# Drive-motor_V1_0_2.net
KiCad netlist of a schematic drawn in Altium Designer
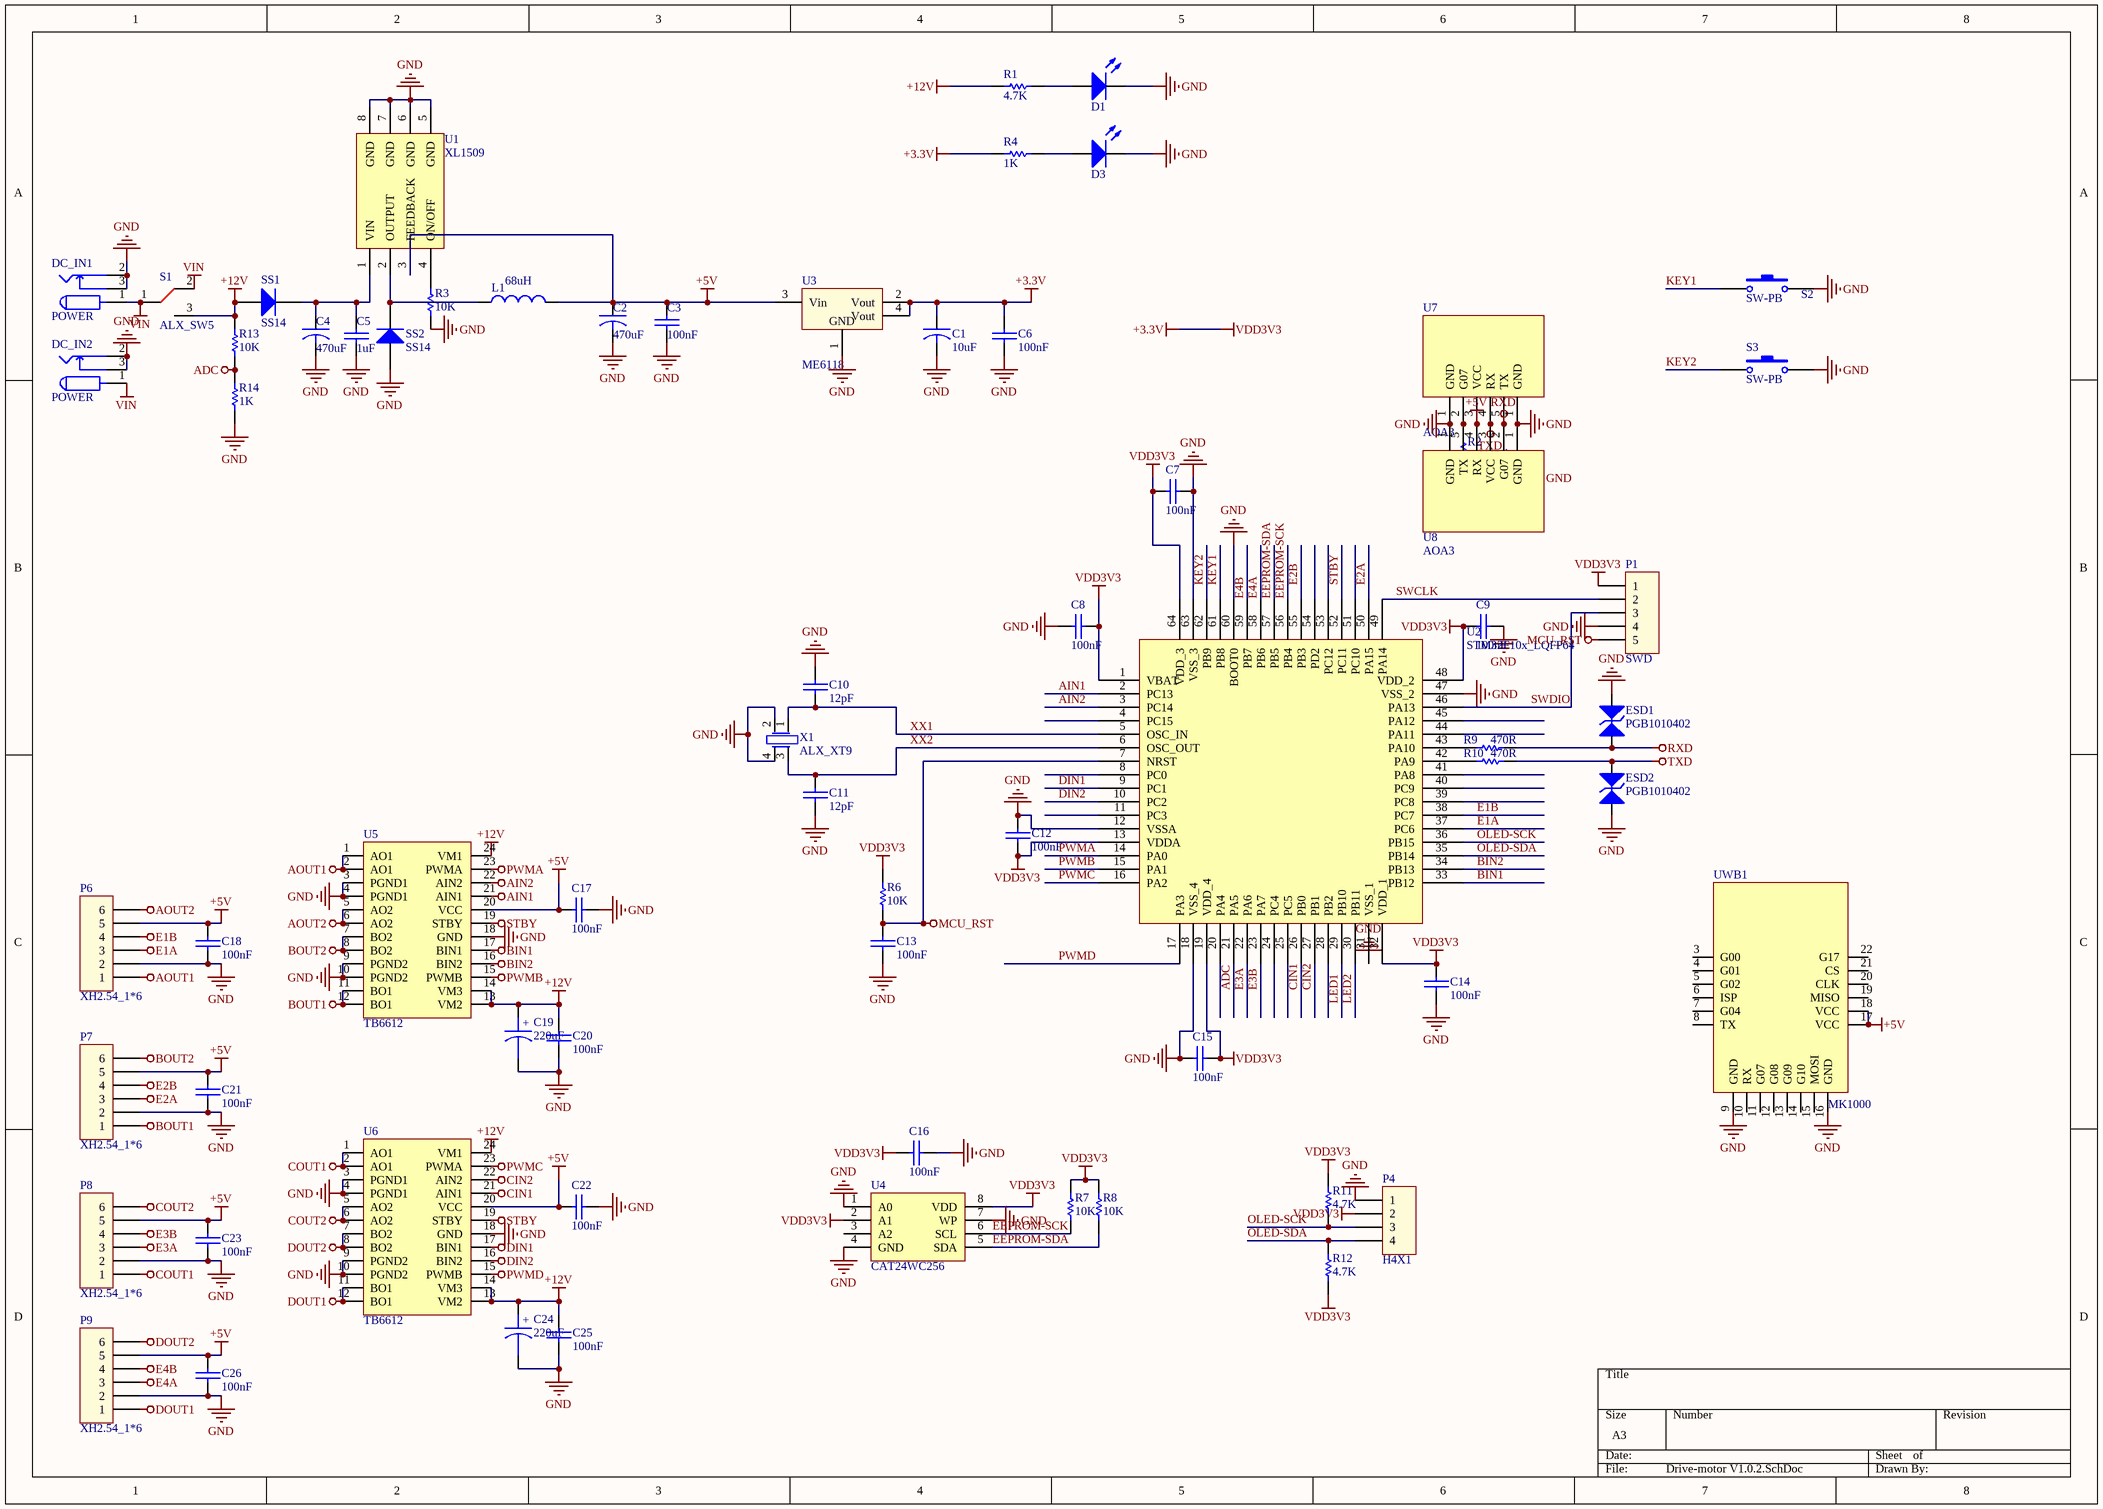
[diagram p0: Drive-motor V1.0.2.SchDoc]

(export (version "E")
  (design (tool "Eeschema 10.0.6"))
  (components
    (comp (ref "C1")
      (value "10uF")
      (footprint "ALX_E")
      (description "Capacitor")
      (libsource (lib "MIAO") (part "ALX_CAPACITOR"))
    )
    (comp (ref "C2")
      (value "470uF")
      (footprint "CAP POL [35V]")
      (description "Capacitor")
      (libsource (lib "MIAO") (part "ALX_CAPACITOR"))
    )
    (comp (ref "C3")
      (value "100nF")
      (footprint "ALX_0603C")
      (description "Capacitor")
      (libsource (lib "MIAO") (part "ALX_CAP"))
    )
    (comp (ref "C4")
      (value "470uF")
      (footprint "CAP POL [35V]")
      (description "Capacitor")
      (libsource (lib "MIAO") (part "ALX_CAPACITOR"))
    )
    (comp (ref "C5")
      (value "1uF")
      (footprint "ALX_0603C")
      (description "Capacitor")
      (libsource (lib "MIAO") (part "ALX_CAP"))
    )
    (comp (ref "C6")
      (value "100nF")
      (footprint "0603C")
      (description "Capacitor")
      (libsource (lib "MIAO") (part "ALX_CAP"))
    )
    (comp (ref "C7")
      (value "100nF")
      (footprint "0603C")
      (description "Capacitor")
      (libsource (lib "MIAO") (part "ALX_CAP"))
    )
    (comp (ref "C8")
      (value "100nF")
      (footprint "0603C")
      (description "Capacitor")
      (libsource (lib "MIAO") (part "ALX_CAP"))
    )
    (comp (ref "C9")
      (value "100nF")
      (footprint "0603C")
      (description "Capacitor")
      (libsource (lib "MIAO") (part "ALX_CAP"))
    )
    (comp (ref "C10")
      (value "12pF")
      (footprint "0603C")
      (description "Capacitor")
      (libsource (lib "MIAO") (part "ALX_CAP"))
    )
    (comp (ref "C11")
      (value "12pF")
      (footprint "0603C")
      (description "Capacitor")
      (libsource (lib "MIAO") (part "ALX_CAP"))
    )
    (comp (ref "C12")
      (value "100nF")
      (footprint "0603C")
      (description "Capacitor")
      (libsource (lib "MIAO") (part "ALX_CAP"))
    )
    (comp (ref "C13")
      (value "100nF")
      (footprint "0603C")
      (description "Capacitor")
      (libsource (lib "MIAO") (part "ALX_CAP"))
    )
    (comp (ref "C14")
      (value "100nF")
      (footprint "0603C")
      (description "Capacitor")
      (libsource (lib "MIAO") (part "ALX_CAP"))
    )
    (comp (ref "C15")
      (value "100nF")
      (footprint "0603C")
      (description "Capacitor")
      (libsource (lib "MIAO") (part "ALX_CAP"))
    )
    (comp (ref "C16")
      (value "100nF")
      (footprint "0603C")
      (description "Capacitor")
      (libsource (lib "MIAO") (part "ALX_CAP"))
    )
    (comp (ref "C17")
      (value "100nF")
      (footprint "0603C")
      (description "Capacitor")
      (libsource (lib "MIAO") (part "ALX_CAP"))
    )
    (comp (ref "C18")
      (value "100nF")
      (footprint "0603C")
      (description "Capacitor")
      (libsource (lib "MIAO") (part "ALX_CAP"))
    )
    (comp (ref "C19")
      (value "Cap Pol")
      (footprint "CAP[1206]")
      (fields (field (name "ALTIUM_UNNAMED_1") "220uF"))
      (libsource (lib "MIAO") (part "Cap Pol"))
    )
    (comp (ref "C20")
      (value "100nF")
      (footprint "0603C")
      (description "Capacitor")
      (libsource (lib "MIAO") (part "ALX_CAP"))
    )
    (comp (ref "C21")
      (value "100nF")
      (footprint "0603C")
      (description "Capacitor")
      (libsource (lib "MIAO") (part "ALX_CAP"))
    )
    (comp (ref "C22")
      (value "100nF")
      (footprint "0603C")
      (description "Capacitor")
      (libsource (lib "MIAO") (part "ALX_CAP"))
    )
    (comp (ref "C23")
      (value "100nF")
      (footprint "0603C")
      (description "Capacitor")
      (libsource (lib "MIAO") (part "ALX_CAP"))
    )
    (comp (ref "C24")
      (value "Cap Pol")
      (footprint "CAP[1206]")
      (fields (field (name "ALTIUM_UNNAMED_1") "220uF"))
      (libsource (lib "MIAO") (part "Cap Pol"))
    )
    (comp (ref "C25")
      (value "100nF")
      (footprint "0603C")
      (description "Capacitor")
      (libsource (lib "MIAO") (part "ALX_CAP"))
    )
    (comp (ref "C26")
      (value "100nF")
      (footprint "0603C")
      (description "Capacitor")
      (libsource (lib "MIAO") (part "ALX_CAP"))
    )
    (comp (ref "D1") (value "LED") (footprint "LED[0603]") (libsource (lib "MIAO") (part "LED")))
    (comp (ref "D2") (value "LED") (footprint "LED[0603]") (libsource (lib "MIAO") (part "LED")))
    (comp (ref "D3") (value "LED") (footprint "LED[0603]") (libsource (lib "MIAO") (part "LED")))
    (comp (ref "DC_IN1") (value "POWER") (footprint "DC10B") (libsource (lib "MIAO") (part "POW")))
    (comp (ref "DC_IN2") (value "POWER") (footprint "DC10B") (libsource (lib "MIAO") (part "POW")))
    (comp (ref "ESD1")
      (value "PGB1010402")
      (footprint "ALX_0402A")
      (description "Zener Diode")
      (libsource (lib "MIAO") (part "PGB1010402"))
    )
    (comp (ref "ESD2")
      (value "PGB1010402")
      (footprint "ALX_0402A")
      (description "Zener Diode")
      (libsource (lib "MIAO") (part "PGB1010402"))
    )
    (comp (ref "L1")
      (value "68uH")
      (footprint "Inductor_0650_47UH")
      (libsource (lib "MIAO") (part "Inductor"))
    )
    (comp (ref "P1")
      (value "SWD")
      (footprint "H2.54-1X5")
      (description "H5X1")
      (libsource (lib "MIAO") (part "H5X1"))
    )
    (comp (ref "P4") (value "H4X1") (footprint "0.96") (libsource (lib "MIAO") (part "H4X1")))
    (comp (ref "P6")
      (value "XH2.54_1*6")
      (footprint "XH2.54-LI-6P")
      (libsource (lib "MIAO") (part "XH2.54_1*6"))
    )
    (comp (ref "P7")
      (value "XH2.54_1*6")
      (footprint "XH2.54-LI-6P")
      (libsource (lib "MIAO") (part "XH2.54_1*6"))
    )
    (comp (ref "P8")
      (value "XH2.54_1*6")
      (footprint "XH2.54-LI-6P")
      (libsource (lib "MIAO") (part "XH2.54_1*6"))
    )
    (comp (ref "P9")
      (value "XH2.54_1*6")
      (footprint "XH2.54-LI-6P")
      (libsource (lib "MIAO") (part "XH2.54_1*6"))
    )
    (comp (ref "R1") (value "4.7K") (footprint "ALX_0603A") (libsource (lib "MIAO") (part "ALX_RES_1")))
    (comp (ref "R2") (value "1K") (footprint "ALX_0603A") (libsource (lib "MIAO") (part "ALX_RES_1")))
    (comp (ref "R3") (value "10K") (footprint "ALX_0603A") (libsource (lib "MIAO") (part "ALX_RES")))
    (comp (ref "R4") (value "1K") (footprint "ALX_0603A") (libsource (lib "MIAO") (part "ALX_RES_1")))
    (comp (ref "R6") (value "10K") (footprint "ALX_0603A") (libsource (lib "MIAO") (part "ALX_RES_1")))
    (comp (ref "R7") (value "10K") (footprint "ALX_0603A") (libsource (lib "MIAO") (part "ALX_RES_1")))
    (comp (ref "R8") (value "10K") (footprint "ALX_0603A") (libsource (lib "MIAO") (part "ALX_RES_1")))
    (comp (ref "R9") (value "470R") (footprint "ALX_0603A") (libsource (lib "MIAO") (part "ALX_RES_1")))
    (comp (ref "R10") (value "470R") (footprint "ALX_0603A") (libsource (lib "MIAO") (part "ALX_RES_1")))
    (comp (ref "R11") (value "4.7K") (footprint "ALX_0603A") (libsource (lib "MIAO") (part "ALX_RES_1")))
    (comp (ref "R12") (value "4.7K") (footprint "ALX_0603A") (libsource (lib "MIAO") (part "ALX_RES_1")))
    (comp (ref "R13") (value "10K") (footprint "ALX_0603A") (libsource (lib "MIAO") (part "ALX_RES_1")))
    (comp (ref "R14") (value "1K") (footprint "ALX_0603A") (libsource (lib "MIAO") (part "ALX_RES_1")))
    (comp (ref "S1")
      (value "ALX_SW5")
      (footprint "ALX_SW5")
      (description "SW")
      (libsource (lib "MIAO") (part "ALX_SW5"))
    )
    (comp (ref "S2")
      (value "SW-PB")
      (footprint "ALX_Key-4 -6")
      (description "Switch")
      (libsource (lib "MIAO") (part "ALX_SW-PB"))
    )
    (comp (ref "S3")
      (value "SW-PB")
      (footprint "ALX_Key-4 -6")
      (description "Switch")
      (libsource (lib "MIAO") (part "ALX_SW-PB"))
    )
    (comp (ref "SS1") (value "SS14") (footprint "ALX_SSx4") (libsource (lib "MIAO") (part "ALX_SS24")))
    (comp (ref "SS2") (value "SS14") (footprint "ALX_SSx4") (libsource (lib "MIAO") (part "ALX_SS24")))
    (comp (ref "U1") (value "XL1509") (footprint "SOP8") (libsource (lib "MIAO") (part "XL1509")))
    (comp (ref "U2")
      (value "STM32F10x_LQFP64")
      (footprint "LQFP64-10*10")
      (libsource (lib "MIAO") (part "STM32F10x_LQFP64"))
    )
    (comp (ref "U3")
      (value "ME6118")
      (footprint "SOT-223(AMS1117-3.3)")
      (libsource (lib "MIAO") (part "AMS1117-3.3"))
    )
    (comp (ref "U4") (value "CAT24WC256") (footprint "SO-8") (libsource (lib "MIAO") (part "FM24C64")))
    (comp (ref "U5") (value "TB6612") (footprint "SSOP24_L") (libsource (lib "MIAO") (part "TB6612")))
    (comp (ref "U6") (value "TB6612") (footprint "SSOP24_L") (libsource (lib "MIAO") (part "TB6612")))
    (comp (ref "U7")
      (value "AOA3")
      (footprint "4ANTA - 3")
      (description "AOA2")
      (libsource (lib "") (part "AOA3_1"))
    )
    (comp (ref "U8")
      (value "AOA3")
      (footprint "4ANTA - 3")
      (description "AOA2")
      (libsource (lib "MIAO") (part "AOA3"))
    )
    (comp (ref "UWB1") (value "MK1000") (footprint "MK1000") (libsource (lib "MIAO") (part "MK1000")))
    (comp (ref "X1")
      (value "ALX_XT9")
      (footprint "ALX_XT-9")
      (description "4 Pin Header")
      (libsource (lib "MIAO") (part "ALX_XT9"))
    )
  )
  (nets
    (net (code "1") (name "+3.3V") (class "Default")
      (node (ref "C1") (pin "1") (pinfunction "1_1") (pintype "passive"))
      (node (ref "C12") (pin "1") (pinfunction "1_1") (pintype "passive"))
      (node (ref "C14") (pin "2") (pinfunction "2_2") (pintype "passive"))
      (node (ref "C15") (pin "1") (pinfunction "1_1") (pintype "passive"))
      (node (ref "C16") (pin "2") (pinfunction "2_2") (pintype "passive"))
      (node (ref "C6") (pin "1") (pinfunction "1_1") (pintype "passive"))
      (node (ref "C7") (pin "1") (pinfunction "1_1") (pintype "passive"))
      (node (ref "C8") (pin "2") (pinfunction "2_2") (pintype "passive"))
      (node (ref "C9") (pin "1") (pinfunction "1_1") (pintype "passive"))
      (node (ref "P1") (pin "1") (pinfunction "1_1") (pintype "passive"))
      (node (ref "P4") (pin "2") (pinfunction "2_2") (pintype "passive"))
      (node (ref "R11") (pin "2") (pinfunction "2_2") (pintype "passive"))
      (node (ref "R12") (pin "1") (pinfunction "1_1") (pintype "passive"))
      (node (ref "R4") (pin "2") (pinfunction "2_2") (pintype "passive"))
      (node (ref "R6") (pin "2") (pinfunction "2_2") (pintype "passive"))
      (node (ref "R7") (pin "2") (pinfunction "2_2") (pintype "passive"))
      (node (ref "R8") (pin "2") (pinfunction "2_2") (pintype "passive"))
      (node (ref "U2") (pin "1") (pinfunction "VBAT_1") (pintype "passive"))
      (node (ref "U2") (pin "13") (pinfunction "VDDA_13") (pintype "passive"))
      (node (ref "U2") (pin "19") (pinfunction "VDD_4_19") (pintype "passive"))
      (node (ref "U2") (pin "32") (pinfunction "VDD_1_32") (pintype "passive"))
      (node (ref "U2") (pin "48") (pinfunction "VDD_2_48") (pintype "passive"))
      (node (ref "U2") (pin "64") (pinfunction "VDD_3_64") (pintype "passive"))
      (node (ref "U3") (pin "2") (pinfunction "Vout_2") (pintype "passive"))
      (node (ref "U3") (pin "4") (pinfunction "Vout_4") (pintype "passive"))
      (node (ref "U4") (pin "2") (pinfunction "A1_2") (pintype "passive"))
      (node (ref "U4") (pin "8") (pinfunction "VDD_8") (pintype "passive"))
    )
    (net (code "2") (name "+5V") (class "Default")
      (node (ref "C17") (pin "2") (pinfunction "2_2") (pintype "passive"))
      (node (ref "C18") (pin "1") (pinfunction "1_1") (pintype "passive"))
      (node (ref "C2") (pin "1") (pinfunction "1_1") (pintype "passive"))
      (node (ref "C21") (pin "1") (pinfunction "1_1") (pintype "passive"))
      (node (ref "C22") (pin "2") (pinfunction "2_2") (pintype "passive"))
      (node (ref "C23") (pin "1") (pinfunction "1_1") (pintype "passive"))
      (node (ref "C26") (pin "1") (pinfunction "1_1") (pintype "passive"))
      (node (ref "C3") (pin "1") (pinfunction "1_1") (pintype "passive"))
      (node (ref "L1") (pin "2") (pinfunction "2_2") (pintype "passive"))
      (node (ref "P6") (pin "5") (pinfunction "5_5") (pintype "passive"))
      (node (ref "P7") (pin "5") (pinfunction "5_5") (pintype "passive"))
      (node (ref "P8") (pin "5") (pinfunction "5_5") (pintype "passive"))
      (node (ref "P9") (pin "5") (pinfunction "5_5") (pintype "passive"))
      (node (ref "U1") (pin "3") (pinfunction "FEEDBACK_3") (pintype "passive"))
      (node (ref "U3") (pin "3") (pinfunction "Vin_3") (pintype "passive"))
      (node (ref "U5") (pin "20") (pinfunction "VCC_20") (pintype "passive"))
      (node (ref "U6") (pin "20") (pinfunction "VCC_20") (pintype "passive"))
      (node (ref "U7") (pin "3") (pinfunction "VCC_3") (pintype "passive"))
      (node (ref "U8") (pin "4") (pinfunction "RX_4") (pintype "passive"))
      (node (ref "UWB1") (pin "17") (pinfunction "VCC_17") (pintype "passive"))
      (node (ref "UWB1") (pin "18") (pinfunction "VCC_18") (pintype "passive"))
    )
    (net (code "3") (name "+12V") (class "Default")
      (node (ref "C19") (pin "1") (pinfunction "1_1") (pintype "passive"))
      (node (ref "C20") (pin "1") (pinfunction "1_1") (pintype "passive"))
      (node (ref "C24") (pin "1") (pinfunction "1_1") (pintype "passive"))
      (node (ref "C25") (pin "1") (pinfunction "1_1") (pintype "passive"))
      (node (ref "R1") (pin "2") (pinfunction "2_2") (pintype "passive"))
      (node (ref "R13") (pin "2") (pinfunction "2_2") (pintype "passive"))
      (node (ref "S1") (pin "3") (pintype "passive"))
      (node (ref "SS1") (pin "1") (pintype "passive"))
      (node (ref "U5") (pin "13") (pinfunction "VM2_13") (pintype "passive"))
      (node (ref "U5") (pin "14") (pinfunction "VM3_14") (pintype "passive"))
      (node (ref "U5") (pin "24") (pinfunction "VM1_24") (pintype "passive"))
      (node (ref "U6") (pin "13") (pinfunction "VM2_13") (pintype "passive"))
      (node (ref "U6") (pin "14") (pinfunction "VM3_14") (pintype "passive"))
      (node (ref "U6") (pin "24") (pinfunction "VM1_24") (pintype "passive"))
    )
    (net (code "4") (name "/EEPROM-SCK") (class "Default")
      (node (ref "R7") (pin "1") (pinfunction "1_1") (pintype "passive"))
      (node (ref "U2") (pin "56") (pinfunction "PB4_56") (pintype "passive"))
      (node (ref "U4") (pin "6") (pinfunction "SCL_6") (pintype "passive"))
    )
    (net (code "5") (name "/EEPROM-SDA") (class "Default")
      (node (ref "R8") (pin "1") (pinfunction "1_1") (pintype "passive"))
      (node (ref "U2") (pin "57") (pinfunction "PB5_57") (pintype "passive"))
      (node (ref "U4") (pin "5") (pinfunction "SDA_5") (pintype "passive"))
    )
    (net (code "6") (name "/KEY1") (class "Default")
      (node (ref "S2") (pin "1") (pinfunction "1_1") (pintype "passive"))
      (node (ref "U2") (pin "61") (pinfunction "PB8_61") (pintype "passive"))
    )
    (net (code "7") (name "/KEY2") (class "Default")
      (node (ref "S3") (pin "1") (pinfunction "1_1") (pintype "passive"))
      (node (ref "U2") (pin "62") (pinfunction "PB9_62") (pintype "passive"))
    )
    (net (code "8") (name "/LED1") (class "Default")
      (node (ref "U2") (pin "29") (pinfunction "PB10_29") (pintype "passive"))
    )
    (net (code "9") (name "/LED2") (class "Default")
      (node (ref "U2") (pin "30") (pinfunction "PB11_30") (pintype "passive"))
    )
    (net (code "10") (name "/OLED-SCK") (class "Default")
      (node (ref "P4") (pin "3") (pinfunction "3_3") (pintype "passive"))
      (node (ref "R11") (pin "1") (pinfunction "1_1") (pintype "passive"))
      (node (ref "U2") (pin "36") (pinfunction "PB15_36") (pintype "passive"))
    )
    (net (code "11") (name "/OLED-SDA") (class "Default")
      (node (ref "P4") (pin "4") (pinfunction "4_4") (pintype "passive"))
      (node (ref "R12") (pin "2") (pinfunction "2_2") (pintype "passive"))
      (node (ref "U2") (pin "35") (pinfunction "PB14_35") (pintype "passive"))
    )
    (net (code "12") (name "/SWCLK") (class "Default")
      (node (ref "P1") (pin "2") (pinfunction "2_2") (pintype "passive"))
      (node (ref "U2") (pin "49") (pinfunction "PA14_49") (pintype "passive"))
    )
    (net (code "13") (name "/SWDIO") (class "Default")
      (node (ref "P1") (pin "3") (pinfunction "3_3") (pintype "passive"))
      (node (ref "U2") (pin "46") (pinfunction "PA13_46") (pintype "passive"))
    )
    (net (code "14") (name "/XX1") (class "Default")
      (node (ref "C10") (pin "1") (pinfunction "1_1") (pintype "passive"))
      (node (ref "U2") (pin "5") (pinfunction "OSC_IN_5") (pintype "passive"))
      (node (ref "X1") (pin "1") (pinfunction "OSCO_1") (pintype "passive"))
    )
    (net (code "15") (name "/XX2") (class "Default")
      (node (ref "C11") (pin "2") (pinfunction "2_2") (pintype "passive"))
      (node (ref "U2") (pin "6") (pinfunction "OSC_OUT_6") (pintype "passive"))
      (node (ref "X1") (pin "3") (pinfunction "OSCI_3") (pintype "passive"))
    )
    (net (code "16") (name "ADC") (class "Default")
      (node (ref "R13") (pin "1") (pinfunction "1_1") (pintype "passive"))
      (node (ref "R14") (pin "2") (pinfunction "2_2") (pintype "passive"))
      (node (ref "U2") (pin "21") (pinfunction "PA5_21") (pintype "passive"))
    )
    (net (code "17") (name "AIN1") (class "Default")
      (node (ref "U2") (pin "2") (pinfunction "PC13_2") (pintype "passive"))
      (node (ref "U5") (pin "21") (pinfunction "AIN1_21") (pintype "passive"))
    )
    (net (code "18") (name "AIN2") (class "Default")
      (node (ref "U2") (pin "3") (pinfunction "PC14_3") (pintype "passive"))
      (node (ref "U5") (pin "22") (pinfunction "AIN2_22") (pintype "passive"))
    )
    (net (code "19") (name "AOUT1") (class "Default")
      (node (ref "P6") (pin "1") (pinfunction "1_1") (pintype "passive"))
      (node (ref "U5") (pin "1") (pinfunction "AO1_1") (pintype "passive"))
      (node (ref "U5") (pin "2") (pinfunction "AO1_2") (pintype "passive"))
    )
    (net (code "20") (name "AOUT2") (class "Default")
      (node (ref "P6") (pin "6") (pinfunction "6_6") (pintype "passive"))
      (node (ref "U5") (pin "5") (pinfunction "AO2_5") (pintype "passive"))
      (node (ref "U5") (pin "6") (pinfunction "AO2_6") (pintype "passive"))
    )
    (net (code "21") (name "BIN1") (class "Default")
      (node (ref "U2") (pin "33") (pinfunction "PB12_33") (pintype "passive"))
      (node (ref "U5") (pin "17") (pinfunction "BIN1_17") (pintype "passive"))
    )
    (net (code "22") (name "BIN2") (class "Default")
      (node (ref "U2") (pin "34") (pinfunction "PB13_34") (pintype "passive"))
      (node (ref "U5") (pin "16") (pinfunction "BIN2_16") (pintype "passive"))
    )
    (net (code "23") (name "BOUT1") (class "Default")
      (node (ref "P7") (pin "1") (pinfunction "1_1") (pintype "passive"))
      (node (ref "U5") (pin "11") (pinfunction "BO1_11") (pintype "passive"))
      (node (ref "U5") (pin "12") (pinfunction "BO1_12") (pintype "passive"))
    )
    (net (code "24") (name "BOUT2") (class "Default")
      (node (ref "P7") (pin "6") (pinfunction "6_6") (pintype "passive"))
      (node (ref "U5") (pin "7") (pinfunction "BO2_7") (pintype "passive"))
      (node (ref "U5") (pin "8") (pinfunction "BO2_8") (pintype "passive"))
    )
    (net (code "25") (name "CIN1") (class "Default")
      (node (ref "U2") (pin "26") (pinfunction "PB0_26") (pintype "passive"))
      (node (ref "U6") (pin "21") (pinfunction "AIN1_21") (pintype "passive"))
    )
    (net (code "26") (name "CIN2") (class "Default")
      (node (ref "U2") (pin "27") (pinfunction "PB1_27") (pintype "passive"))
      (node (ref "U6") (pin "22") (pinfunction "AIN2_22") (pintype "passive"))
    )
    (net (code "27") (name "COUT1") (class "Default")
      (node (ref "P8") (pin "1") (pinfunction "1_1") (pintype "passive"))
      (node (ref "U6") (pin "1") (pinfunction "AO1_1") (pintype "passive"))
      (node (ref "U6") (pin "2") (pinfunction "AO1_2") (pintype "passive"))
    )
    (net (code "28") (name "COUT2") (class "Default")
      (node (ref "P8") (pin "6") (pinfunction "6_6") (pintype "passive"))
      (node (ref "U6") (pin "5") (pinfunction "AO2_5") (pintype "passive"))
      (node (ref "U6") (pin "6") (pinfunction "AO2_6") (pintype "passive"))
    )
    (net (code "29") (name "DIN1") (class "Default")
      (node (ref "U2") (pin "9") (pinfunction "PC1_9") (pintype "passive"))
      (node (ref "U6") (pin "17") (pinfunction "BIN1_17") (pintype "passive"))
    )
    (net (code "30") (name "DIN2") (class "Default")
      (node (ref "U2") (pin "10") (pinfunction "PC2_10") (pintype "passive"))
      (node (ref "U6") (pin "16") (pinfunction "BIN2_16") (pintype "passive"))
    )
    (net (code "31") (name "DOUT1") (class "Default")
      (node (ref "P9") (pin "1") (pinfunction "1_1") (pintype "passive"))
      (node (ref "U6") (pin "11") (pinfunction "BO1_11") (pintype "passive"))
      (node (ref "U6") (pin "12") (pinfunction "BO1_12") (pintype "passive"))
    )
    (net (code "32") (name "DOUT2") (class "Default")
      (node (ref "P9") (pin "6") (pinfunction "6_6") (pintype "passive"))
      (node (ref "U6") (pin "7") (pinfunction "BO2_7") (pintype "passive"))
      (node (ref "U6") (pin "8") (pinfunction "BO2_8") (pintype "passive"))
    )
    (net (code "33") (name "E1A") (class "Default")
      (node (ref "P6") (pin "3") (pinfunction "3_3") (pintype "passive"))
      (node (ref "U2") (pin "37") (pinfunction "PC6_37") (pintype "passive"))
    )
    (net (code "34") (name "E1B") (class "Default")
      (node (ref "P6") (pin "4") (pinfunction "4_4") (pintype "passive"))
      (node (ref "U2") (pin "38") (pinfunction "PC7_38") (pintype "passive"))
    )
    (net (code "35") (name "E2A") (class "Default")
      (node (ref "P7") (pin "3") (pinfunction "3_3") (pintype "passive"))
      (node (ref "U2") (pin "50") (pinfunction "PA15_50") (pintype "passive"))
    )
    (net (code "36") (name "E2B") (class "Default")
      (node (ref "P7") (pin "4") (pinfunction "4_4") (pintype "passive"))
      (node (ref "U2") (pin "55") (pinfunction "PB3_55") (pintype "passive"))
    )
    (net (code "37") (name "E3A") (class "Default")
      (node (ref "P8") (pin "3") (pinfunction "3_3") (pintype "passive"))
      (node (ref "U2") (pin "22") (pinfunction "PA6_22") (pintype "passive"))
    )
    (net (code "38") (name "E3B") (class "Default")
      (node (ref "P8") (pin "4") (pinfunction "4_4") (pintype "passive"))
      (node (ref "U2") (pin "23") (pinfunction "PA7_23") (pintype "passive"))
    )
    (net (code "39") (name "E4A") (class "Default")
      (node (ref "P9") (pin "3") (pinfunction "3_3") (pintype "passive"))
      (node (ref "U2") (pin "58") (pinfunction "PB6_58") (pintype "passive"))
    )
    (net (code "40") (name "E4B") (class "Default")
      (node (ref "P9") (pin "4") (pinfunction "4_4") (pintype "passive"))
      (node (ref "U2") (pin "59") (pinfunction "PB7_59") (pintype "passive"))
    )
    (net (code "41") (name "GND") (class "Default")
      (node (ref "C1") (pin "2") (pinfunction "2_2") (pintype "passive"))
      (node (ref "C10") (pin "2") (pinfunction "2_2") (pintype "passive"))
      (node (ref "C11") (pin "1") (pinfunction "1_1") (pintype "passive"))
      (node (ref "C12") (pin "2") (pinfunction "2_2") (pintype "passive"))
      (node (ref "C13") (pin "1") (pinfunction "1_1") (pintype "passive"))
      (node (ref "C14") (pin "1") (pinfunction "1_1") (pintype "passive"))
      (node (ref "C15") (pin "2") (pinfunction "2_2") (pintype "passive"))
      (node (ref "C16") (pin "1") (pinfunction "1_1") (pintype "passive"))
      (node (ref "C17") (pin "1") (pinfunction "1_1") (pintype "passive"))
      (node (ref "C18") (pin "2") (pinfunction "2_2") (pintype "passive"))
      (node (ref "C19") (pin "2") (pinfunction "2_2") (pintype "passive"))
      (node (ref "C2") (pin "2") (pinfunction "2_2") (pintype "passive"))
      (node (ref "C20") (pin "2") (pinfunction "2_2") (pintype "passive"))
      (node (ref "C21") (pin "2") (pinfunction "2_2") (pintype "passive"))
      (node (ref "C22") (pin "1") (pinfunction "1_1") (pintype "passive"))
      (node (ref "C23") (pin "2") (pinfunction "2_2") (pintype "passive"))
      (node (ref "C24") (pin "2") (pinfunction "2_2") (pintype "passive"))
      (node (ref "C25") (pin "2") (pinfunction "2_2") (pintype "passive"))
      (node (ref "C26") (pin "2") (pinfunction "2_2") (pintype "passive"))
      (node (ref "C3") (pin "2") (pinfunction "2_2") (pintype "passive"))
      (node (ref "C4") (pin "2") (pinfunction "2_2") (pintype "passive"))
      (node (ref "C5") (pin "2") (pinfunction "2_2") (pintype "passive"))
      (node (ref "C6") (pin "2") (pinfunction "2_2") (pintype "passive"))
      (node (ref "C7") (pin "2") (pinfunction "2_2") (pintype "passive"))
      (node (ref "C8") (pin "1") (pinfunction "1_1") (pintype "passive"))
      (node (ref "C9") (pin "2") (pinfunction "2_2") (pintype "passive"))
      (node (ref "D1") (pin "2") (pinfunction "K_2") (pintype "passive"))
      (node (ref "D2") (pin "2") (pinfunction "K_2") (pintype "passive"))
      (node (ref "D3") (pin "2") (pinfunction "K_2") (pintype "passive"))
      (node (ref "DC_IN1") (pin "2") (pintype "passive"))
      (node (ref "DC_IN1") (pin "3") (pintype "passive"))
      (node (ref "DC_IN2") (pin "2") (pintype "passive"))
      (node (ref "DC_IN2") (pin "3") (pintype "passive"))
      (node (ref "ESD1") (pin "1") (pinfunction "A_1") (pintype "passive"))
      (node (ref "ESD2") (pin "2") (pinfunction "K_2") (pintype "passive"))
      (node (ref "P1") (pin "4") (pinfunction "4_4") (pintype "passive"))
      (node (ref "P4") (pin "1") (pinfunction "1_1") (pintype "passive"))
      (node (ref "P6") (pin "2") (pinfunction "2_2") (pintype "passive"))
      (node (ref "P7") (pin "2") (pinfunction "2_2") (pintype "passive"))
      (node (ref "P8") (pin "2") (pinfunction "2_2") (pintype "passive"))
      (node (ref "P9") (pin "2") (pinfunction "2_2") (pintype "passive"))
      (node (ref "R14") (pin "1") (pinfunction "1_1") (pintype "passive"))
      (node (ref "R3") (pin "1") (pinfunction "1_1") (pintype "passive"))
      (node (ref "S2") (pin "2") (pinfunction "2_2") (pintype "passive"))
      (node (ref "S3") (pin "2") (pinfunction "2_2") (pintype "passive"))
      (node (ref "SS2") (pin "1") (pintype "passive"))
      (node (ref "U1") (pin "5") (pinfunction "GND_5") (pintype "passive"))
      (node (ref "U1") (pin "6") (pinfunction "GND_6") (pintype "passive"))
      (node (ref "U1") (pin "7") (pinfunction "GND_7") (pintype "passive"))
      (node (ref "U1") (pin "8") (pinfunction "GND_8") (pintype "passive"))
      (node (ref "U2") (pin "12") (pinfunction "VSSA_12") (pintype "passive"))
      (node (ref "U2") (pin "18") (pinfunction "VSS_4_18") (pintype "passive"))
      (node (ref "U2") (pin "31") (pinfunction "VSS_1_31") (pintype "passive"))
      (node (ref "U2") (pin "47") (pinfunction "VSS_2_47") (pintype "passive"))
      (node (ref "U2") (pin "60") (pinfunction "BOOT0_60") (pintype "passive"))
      (node (ref "U2") (pin "63") (pinfunction "VSS_3_63") (pintype "passive"))
      (node (ref "U3") (pin "1") (pinfunction "GND_1") (pintype "passive"))
      (node (ref "U4") (pin "1") (pinfunction "A0_1") (pintype "passive"))
      (node (ref "U4") (pin "4") (pinfunction "GND_4") (pintype "passive"))
      (node (ref "U4") (pin "7") (pinfunction "WP_7") (pintype "passive"))
      (node (ref "U5") (pin "10") (pinfunction "PGND2_10") (pintype "passive"))
      (node (ref "U5") (pin "18") (pinfunction "GND_18") (pintype "passive"))
      (node (ref "U5") (pin "3") (pinfunction "PGND1_3") (pintype "passive"))
      (node (ref "U5") (pin "4") (pinfunction "PGND1_4") (pintype "passive"))
      (node (ref "U5") (pin "9") (pinfunction "PGND2_9") (pintype "passive"))
      (node (ref "U6") (pin "10") (pinfunction "PGND2_10") (pintype "passive"))
      (node (ref "U6") (pin "18") (pinfunction "GND_18") (pintype "passive"))
      (node (ref "U6") (pin "3") (pinfunction "PGND1_3") (pintype "passive"))
      (node (ref "U6") (pin "4") (pinfunction "PGND1_4") (pintype "passive"))
      (node (ref "U6") (pin "9") (pinfunction "PGND2_9") (pintype "passive"))
      (node (ref "U7") (pin "1") (pinfunction "GND_1") (pintype "passive"))
      (node (ref "U8") (pin "1") (pinfunction "GND_1") (pintype "passive"))
      (node (ref "UWB1") (pin "16") (pinfunction "GND_16") (pintype "passive"))
      (node (ref "UWB1") (pin "9") (pinfunction "GND_9") (pintype "passive"))
      (node (ref "X1") (pin "2") (pinfunction "GND_2") (pintype "passive"))
      (node (ref "X1") (pin "4") (pinfunction "GND_4") (pintype "passive"))
    )
    (net (code "42") (name "MCU_RST") (class "Default")
      (node (ref "C13") (pin "2") (pinfunction "2_2") (pintype "passive"))
      (node (ref "P1") (pin "5") (pinfunction "5_5") (pintype "passive"))
      (node (ref "R6") (pin "1") (pinfunction "1_1") (pintype "passive"))
      (node (ref "U2") (pin "7") (pinfunction "NRST_7") (pintype "passive"))
    )
    (net (code "43") (name "Net-(D1-A)") (class "Default")
      (node (ref "D1") (pin "1") (pinfunction "A_1") (pintype "passive"))
      (node (ref "R1") (pin "1") (pinfunction "1_1") (pintype "passive"))
    )
    (net (code "44") (name "Net-(D2-A)") (class "Default")
      (node (ref "D2") (pin "1") (pinfunction "A_1") (pintype "passive"))
      (node (ref "R2") (pin "2") (pinfunction "2_2") (pintype "passive"))
    )
    (net (code "45") (name "Net-(D3-A)") (class "Default")
      (node (ref "D3") (pin "1") (pinfunction "A_1") (pintype "passive"))
      (node (ref "R4") (pin "1") (pinfunction "1_1") (pintype "passive"))
    )
    (net (code "46") (name "Net-(U1-ON{slash}OFF)") (class "Default")
      (node (ref "R3") (pin "2") (pinfunction "2_2") (pintype "passive"))
      (node (ref "U1") (pin "4") (pinfunction "ON/OFF_4") (pintype "passive"))
    )
    (net (code "47") (name "Net-(U1-OUTPUT)") (class "Default")
      (node (ref "L1") (pin "1") (pinfunction "1_1") (pintype "passive"))
      (node (ref "SS2") (pin "2") (pintype "passive"))
      (node (ref "U1") (pin "2") (pinfunction "OUTPUT_2") (pintype "passive"))
    )
    (net (code "48") (name "Net-(U1-VIN)") (class "Default")
      (node (ref "C4") (pin "1") (pinfunction "1_1") (pintype "passive"))
      (node (ref "C5") (pin "1") (pinfunction "1_1") (pintype "passive"))
      (node (ref "SS1") (pin "2") (pintype "passive"))
      (node (ref "U1") (pin "1") (pinfunction "VIN_1") (pintype "passive"))
    )
    (net (code "49") (name "Net-(U2-PA9)") (class "Default")
      (node (ref "R10") (pin "1") (pinfunction "1_1") (pintype "passive"))
      (node (ref "U2") (pin "42") (pinfunction "PA9_42") (pintype "passive"))
    )
    (net (code "50") (name "Net-(U2-PA10)") (class "Default")
      (node (ref "R9") (pin "1") (pinfunction "1_1") (pintype "passive"))
      (node (ref "U2") (pin "43") (pinfunction "PA10_43") (pintype "passive"))
    )
    (net (code "51") (name "Net-(U7-G07)") (class "Default")
      (node (ref "R2") (pin "1") (pinfunction "1_1") (pintype "passive"))
      (node (ref "U7") (pin "2") (pinfunction "G07_2") (pintype "passive"))
      (node (ref "U8") (pin "5") (pinfunction "TX_5") (pintype "passive"))
    )
    (net (code "52") (name "PWMA") (class "Default")
      (node (ref "U2") (pin "14") (pinfunction "PA0_14") (pintype "passive"))
      (node (ref "U5") (pin "23") (pinfunction "PWMA_23") (pintype "passive"))
    )
    (net (code "53") (name "PWMB") (class "Default")
      (node (ref "U2") (pin "15") (pinfunction "PA1_15") (pintype "passive"))
      (node (ref "U5") (pin "15") (pinfunction "PWMB_15") (pintype "passive"))
    )
    (net (code "54") (name "PWMC") (class "Default")
      (node (ref "U2") (pin "16") (pinfunction "PA2_16") (pintype "passive"))
      (node (ref "U6") (pin "23") (pinfunction "PWMA_23") (pintype "passive"))
    )
    (net (code "55") (name "PWMD") (class "Default")
      (node (ref "U2") (pin "17") (pinfunction "PA3_17") (pintype "passive"))
      (node (ref "U6") (pin "15") (pinfunction "PWMB_15") (pintype "passive"))
    )
    (net (code "56") (name "RXD") (class "Default")
      (node (ref "ESD1") (pin "2") (pinfunction "K_2") (pintype "passive"))
      (node (ref "R9") (pin "2") (pinfunction "2_2") (pintype "passive"))
      (node (ref "U7") (pin "5") (pinfunction "TX_5") (pintype "passive"))
      (node (ref "U8") (pin "2") (pinfunction "G07_2") (pintype "passive"))
    )
    (net (code "57") (name "STBY") (class "Default")
      (node (ref "U2") (pin "52") (pinfunction "PC11_52") (pintype "passive"))
      (node (ref "U5") (pin "19") (pinfunction "STBY_19") (pintype "passive"))
      (node (ref "U6") (pin "19") (pinfunction "STBY_19") (pintype "passive"))
    )
    (net (code "58") (name "TXD") (class "Default")
      (node (ref "ESD2") (pin "1") (pinfunction "A_1") (pintype "passive"))
      (node (ref "R10") (pin "2") (pinfunction "2_2") (pintype "passive"))
      (node (ref "U7") (pin "4") (pinfunction "RX_4") (pintype "passive"))
      (node (ref "U8") (pin "3") (pinfunction "VCC_3") (pintype "passive"))
    )
    (net (code "59") (name "VIN") (class "Default")
      (node (ref "DC_IN1") (pin "1") (pintype "passive"))
      (node (ref "DC_IN2") (pin "1") (pintype "passive"))
      (node (ref "S1") (pin "1") (pintype "passive"))
      (node (ref "S1") (pin "2") (pintype "passive"))
    )
    (net (code "60") (name "unconnected-(U2-PA4-Pad20)") (class "Default")
      (node (ref "U2") (pin "20") (pinfunction "PA4_20") (pintype "passive"))
    )
    (net (code "61") (name "unconnected-(U2-PA8-Pad41)") (class "Default")
      (node (ref "U2") (pin "41") (pinfunction "PA8_41") (pintype "passive"))
    )
    (net (code "62") (name "unconnected-(U2-PA11-Pad44)") (class "Default")
      (node (ref "U2") (pin "44") (pinfunction "PA11_44") (pintype "passive"))
    )
    (net (code "63") (name "unconnected-(U2-PA12-Pad45)") (class "Default")
      (node (ref "U2") (pin "45") (pinfunction "PA12_45") (pintype "passive"))
    )
    (net (code "64") (name "unconnected-(U2-PB2-Pad28)") (class "Default")
      (node (ref "U2") (pin "28") (pinfunction "PB2_28") (pintype "passive"))
    )
    (net (code "65") (name "unconnected-(U2-PC0-Pad8)") (class "Default")
      (node (ref "U2") (pin "8") (pinfunction "PC0_8") (pintype "passive"))
    )
    (net (code "66") (name "unconnected-(U2-PC3-Pad11)") (class "Default")
      (node (ref "U2") (pin "11") (pinfunction "PC3_11") (pintype "passive"))
    )
    (net (code "67") (name "unconnected-(U2-PC4-Pad24)") (class "Default")
      (node (ref "U2") (pin "24") (pinfunction "PC4_24") (pintype "passive"))
    )
    (net (code "68") (name "unconnected-(U2-PC5-Pad25)") (class "Default")
      (node (ref "U2") (pin "25") (pinfunction "PC5_25") (pintype "passive"))
    )
    (net (code "69") (name "unconnected-(U2-PC8-Pad39)") (class "Default")
      (node (ref "U2") (pin "39") (pinfunction "PC8_39") (pintype "passive"))
    )
    (net (code "70") (name "unconnected-(U2-PC9-Pad40)") (class "Default")
      (node (ref "U2") (pin "40") (pinfunction "PC9_40") (pintype "passive"))
    )
    (net (code "71") (name "unconnected-(U2-PC10-Pad51)") (class "Default")
      (node (ref "U2") (pin "51") (pinfunction "PC10_51") (pintype "passive"))
    )
    (net (code "72") (name "unconnected-(U2-PC12-Pad53)") (class "Default")
      (node (ref "U2") (pin "53") (pinfunction "PC12_53") (pintype "passive"))
    )
    (net (code "73") (name "unconnected-(U2-PC15-Pad4)") (class "Default")
      (node (ref "U2") (pin "4") (pinfunction "PC15_4") (pintype "passive"))
    )
    (net (code "74") (name "unconnected-(U2-PD2-Pad54)") (class "Default")
      (node (ref "U2") (pin "54") (pinfunction "PD2_54") (pintype "passive"))
    )
    (net (code "75") (name "unconnected-(U4-A2-Pad3)") (class "Default")
      (node (ref "U4") (pin "3") (pinfunction "A2_3") (pintype "passive"))
    )
    (net (code "76") (name "unconnected-(UWB1-CLK-Pad20)") (class "Default")
      (node (ref "UWB1") (pin "20") (pinfunction "CLK_20") (pintype "passive"))
    )
    (net (code "77") (name "unconnected-(UWB1-CS-Pad21)") (class "Default")
      (node (ref "UWB1") (pin "21") (pinfunction "CS_21") (pintype "passive"))
    )
    (net (code "78") (name "unconnected-(UWB1-G00-Pad3)") (class "Default")
      (node (ref "UWB1") (pin "3") (pinfunction "G00_3") (pintype "passive"))
    )
    (net (code "79") (name "unconnected-(UWB1-G01-Pad4)") (class "Default")
      (node (ref "UWB1") (pin "4") (pinfunction "G01_4") (pintype "passive"))
    )
    (net (code "80") (name "unconnected-(UWB1-G02-Pad5)") (class "Default")
      (node (ref "UWB1") (pin "5") (pinfunction "G02_5") (pintype "passive"))
    )
    (net (code "81") (name "unconnected-(UWB1-G04-Pad7)") (class "Default")
      (node (ref "UWB1") (pin "7") (pinfunction "G04_7") (pintype "passive"))
    )
    (net (code "82") (name "unconnected-(UWB1-G07-Pad11)") (class "Default")
      (node (ref "UWB1") (pin "11") (pinfunction "G07_11") (pintype "passive"))
    )
    (net (code "83") (name "unconnected-(UWB1-G08-Pad12)") (class "Default")
      (node (ref "UWB1") (pin "12") (pinfunction "G08_12") (pintype "passive"))
    )
    (net (code "84") (name "unconnected-(UWB1-G09-Pad13)") (class "Default")
      (node (ref "UWB1") (pin "13") (pinfunction "G09_13") (pintype "passive"))
    )
    (net (code "85") (name "unconnected-(UWB1-G10-Pad14)") (class "Default")
      (node (ref "UWB1") (pin "14") (pinfunction "G10_14") (pintype "passive"))
    )
    (net (code "86") (name "unconnected-(UWB1-G17-Pad22)") (class "Default")
      (node (ref "UWB1") (pin "22") (pinfunction "G17_22") (pintype "passive"))
    )
    (net (code "87") (name "unconnected-(UWB1-ISP-Pad6)") (class "Default")
      (node (ref "UWB1") (pin "6") (pinfunction "ISP_6") (pintype "passive"))
    )
    (net (code "88") (name "unconnected-(UWB1-MISO-Pad19)") (class "Default")
      (node (ref "UWB1") (pin "19") (pinfunction "MISO_19") (pintype "passive"))
    )
    (net (code "89") (name "unconnected-(UWB1-MOSI-Pad15)") (class "Default")
      (node (ref "UWB1") (pin "15") (pinfunction "MOSI_15") (pintype "passive"))
    )
    (net (code "90") (name "unconnected-(UWB1-RX-Pad10)") (class "Default")
      (node (ref "UWB1") (pin "10") (pinfunction "RX_10") (pintype "passive"))
    )
    (net (code "91") (name "unconnected-(UWB1-TX-Pad8)") (class "Default")
      (node (ref "UWB1") (pin "8") (pinfunction "TX_8") (pintype "passive"))
    )
  )
)
